# Main.net
KiCad netlist of a schematic drawn in Altium Designer
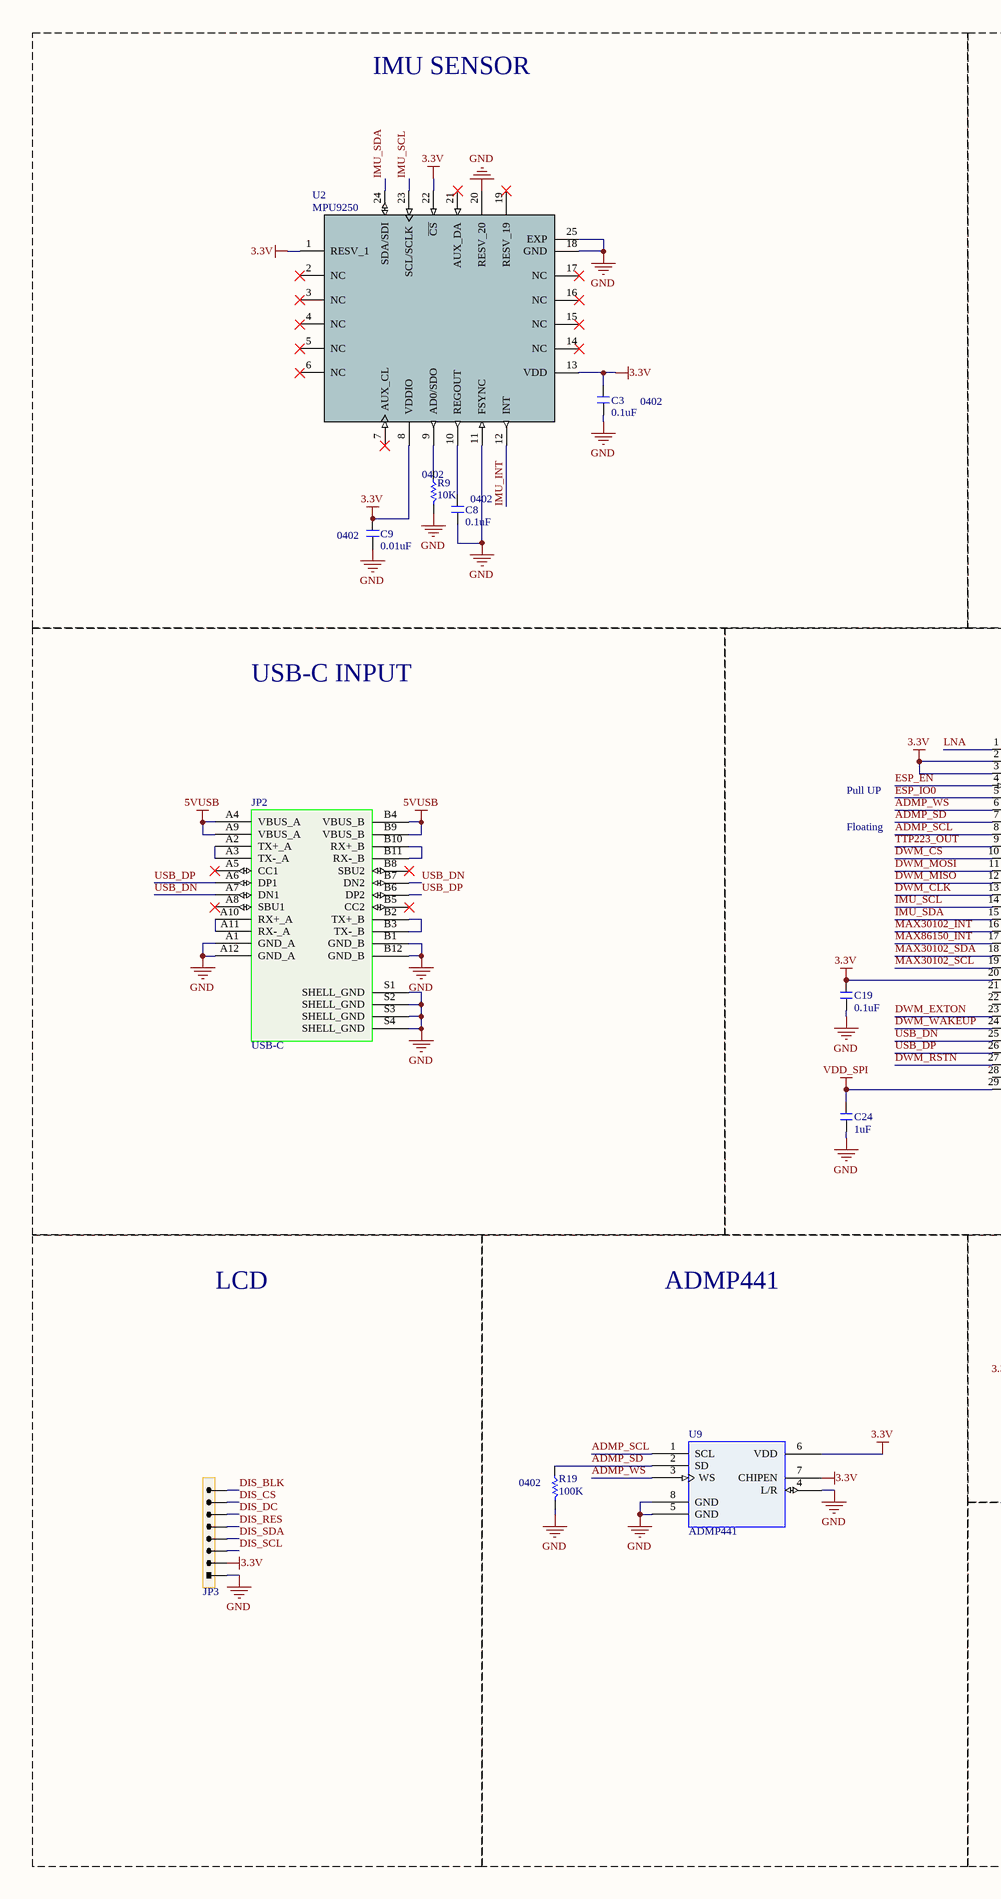
[diagram p0: Main.SchDoc, left]
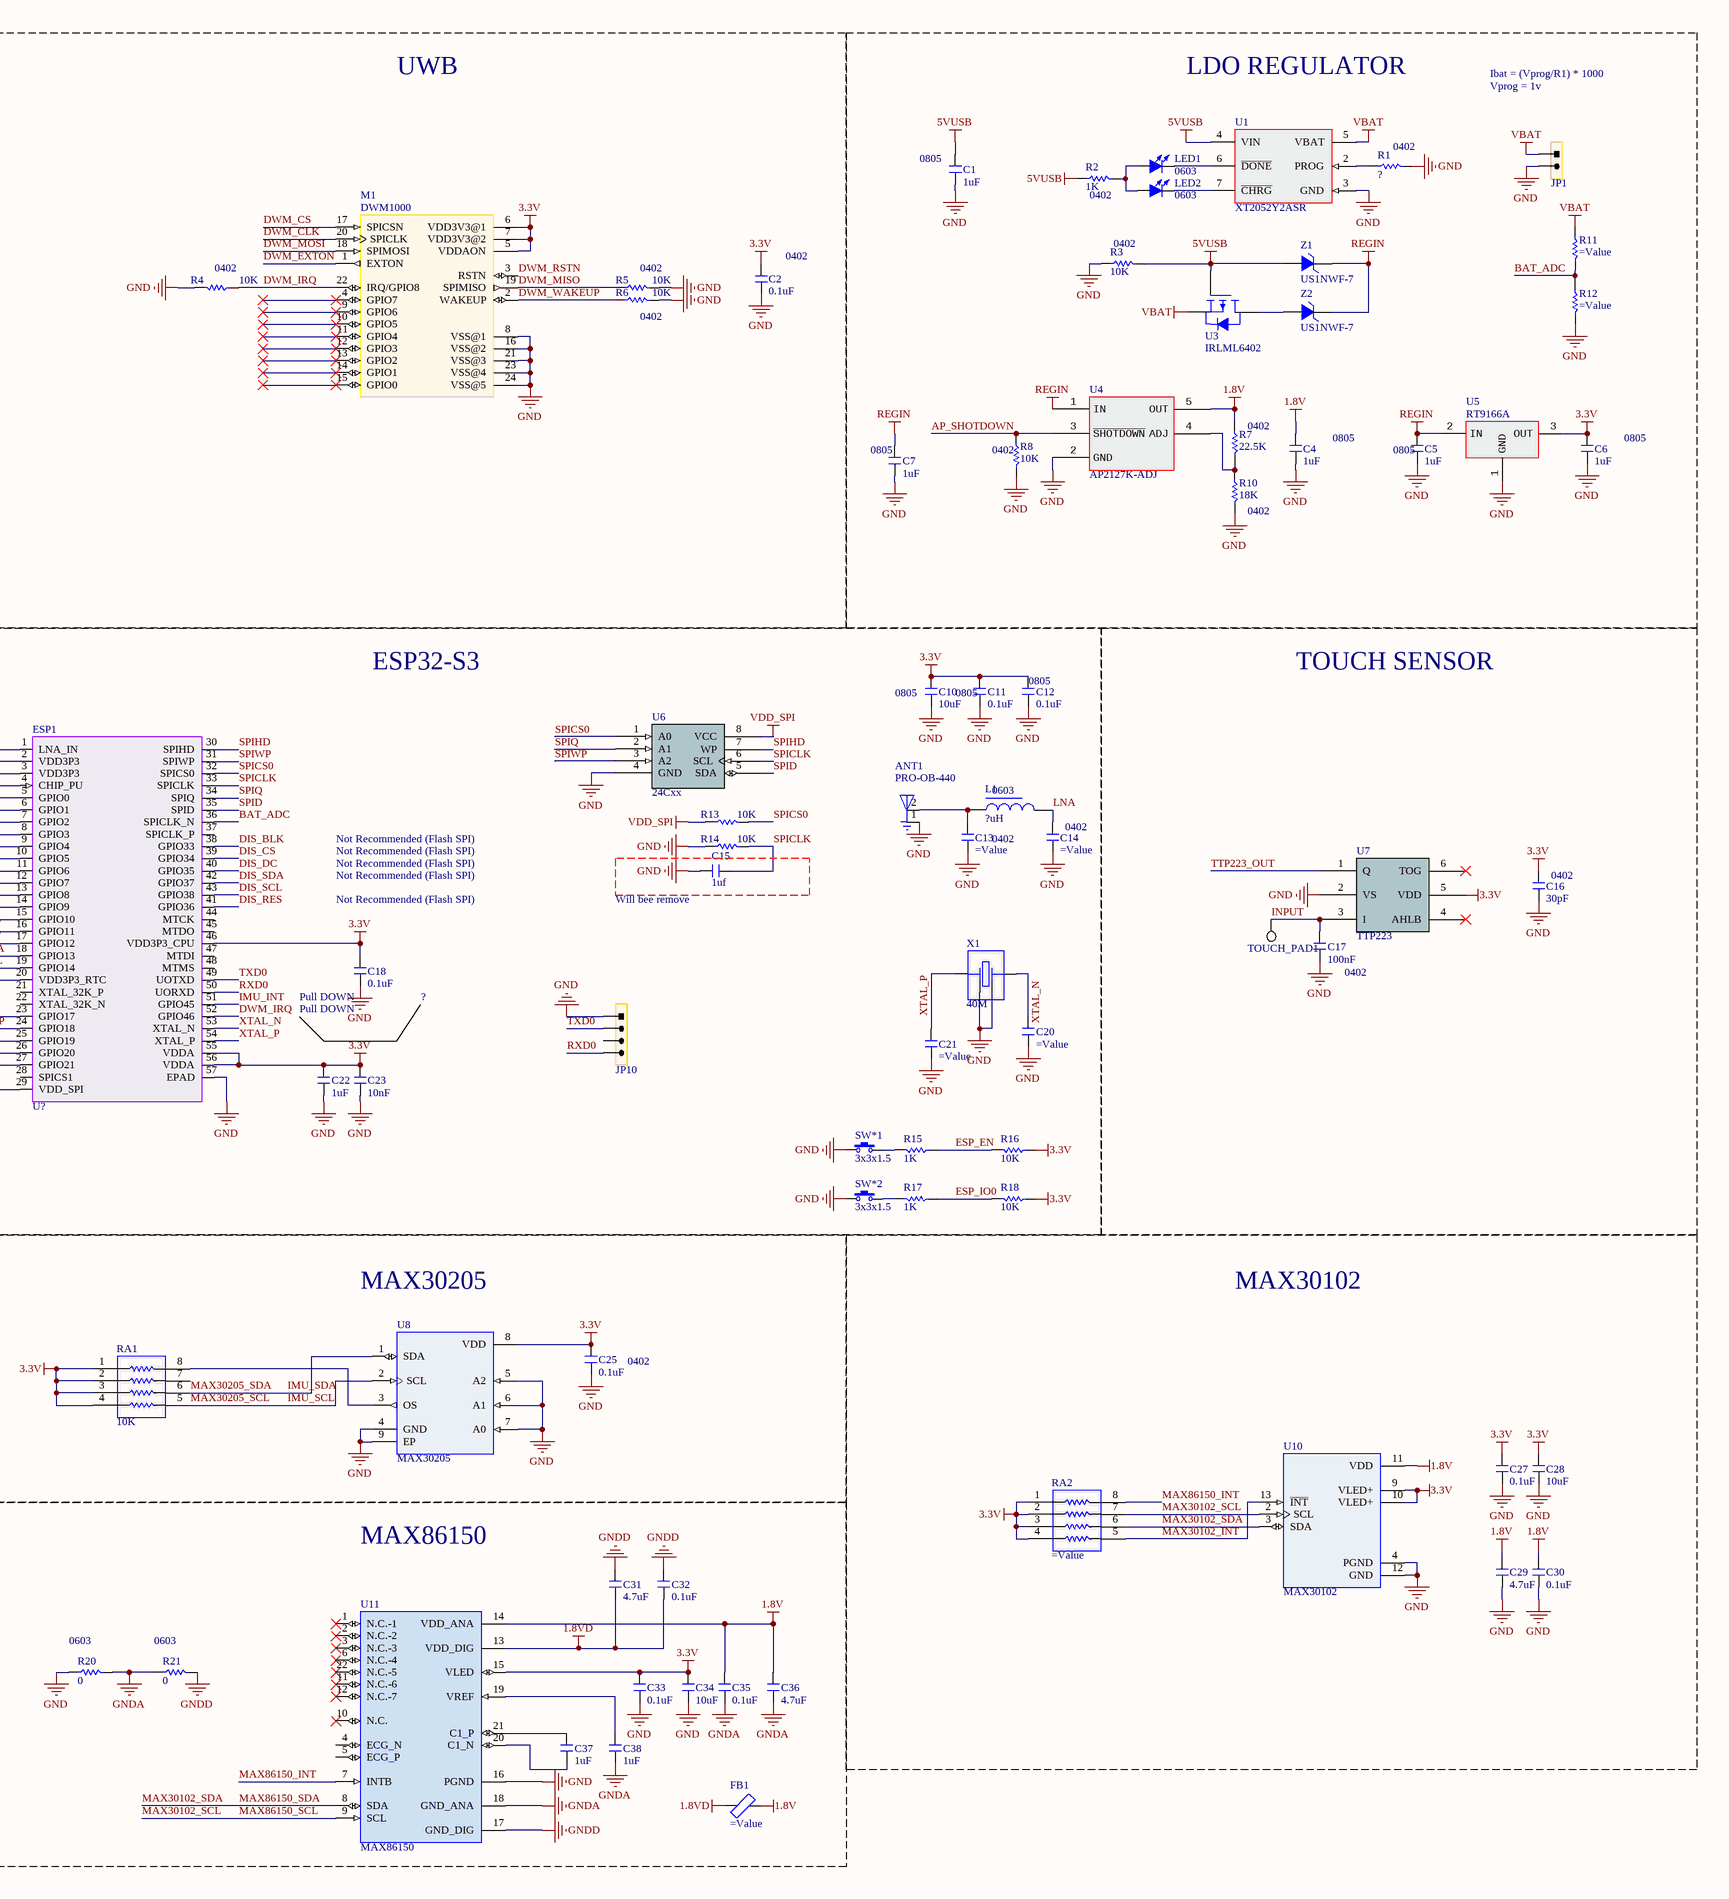
[diagram p1: Main.SchDoc, right]

(export (version "E")
  (design (tool "Eeschema 10.0.6"))
  (components
    (comp (ref "ANT1")
      (value "PRO-OB-440")
      (footprint "PRO-OB-440")
      (libsource (lib "Antenna") (part "PRO-OB-440"))
    )
    (comp (ref "C1")
      (value "1uF")
      (footprint "C 0805")
      (description "Non-polar patch capacitor")
      (fields (field (name "版权归属") "源创客"))
      (libsource (lib "Passive (Resistor-Capacitor-Inductor-Veristor-Ferrite)") (part "C"))
    )
    (comp (ref "C2")
      (value "0.1uF")
      (footprint "C 0402")
      (description "Non-polar patch capacitor")
      (fields (field (name "版权归属") "源创客"))
      (libsource (lib "Passive (Resistor-Capacitor-Inductor-Veristor-Ferrite)") (part "C"))
    )
    (comp (ref "C3")
      (value "0.1uF")
      (footprint "C 0603")
      (description "Non-polar patch capacitor")
      (fields (field (name "版权归属") "源创客"))
      (libsource (lib "Passive (Resistor-Capacitor-Inductor-Veristor-Ferrite)") (part "C"))
    )
    (comp (ref "C4")
      (value "1uF")
      (footprint "C 0805")
      (description "Non-polar patch capacitor")
      (fields (field (name "版权归属") "源创客"))
      (libsource (lib "Passive (Resistor-Capacitor-Inductor-Veristor-Ferrite)") (part "C"))
    )
    (comp (ref "C5")
      (value "1uF")
      (footprint "C 0805")
      (description "Non-polar patch capacitor")
      (fields (field (name "版权归属") "源创客"))
      (libsource (lib "Passive (Resistor-Capacitor-Inductor-Veristor-Ferrite)") (part "C"))
    )
    (comp (ref "C6")
      (value "1uF")
      (footprint "C 0805")
      (description "Non-polar patch capacitor")
      (fields (field (name "版权归属") "源创客"))
      (libsource (lib "Passive (Resistor-Capacitor-Inductor-Veristor-Ferrite)") (part "C"))
    )
    (comp (ref "C7")
      (value "1uF")
      (footprint "C 0805")
      (description "Non-polar patch capacitor")
      (fields (field (name "版权归属") "源创客"))
      (libsource (lib "Passive (Resistor-Capacitor-Inductor-Veristor-Ferrite)") (part "C"))
    )
    (comp (ref "C8")
      (value "0.1uF")
      (footprint "C 0603")
      (description "Non-polar patch capacitor")
      (fields (field (name "版权归属") "源创客"))
      (libsource (lib "Passive (Resistor-Capacitor-Inductor-Veristor-Ferrite)") (part "C"))
    )
    (comp (ref "C9")
      (value "0.01uF")
      (footprint "C 0603")
      (description "Non-polar patch capacitor")
      (fields (field (name "版权归属") "源创客"))
      (libsource (lib "Passive (Resistor-Capacitor-Inductor-Veristor-Ferrite)") (part "C"))
    )
    (comp (ref "C10")
      (value "10uF")
      (footprint "C 0603")
      (description "Non-polar patch capacitor")
      (fields (field (name "版权归属") "源创客"))
      (libsource (lib "Passive (Resistor-Capacitor-Inductor-Veristor-Ferrite)") (part "C"))
    )
    (comp (ref "C11")
      (value "0.1uF")
      (footprint "C 0603")
      (description "Non-polar patch capacitor")
      (fields (field (name "版权归属") "源创客"))
      (libsource (lib "Passive (Resistor-Capacitor-Inductor-Veristor-Ferrite)") (part "C"))
    )
    (comp (ref "C12")
      (value "0.1uF")
      (footprint "C 0603")
      (description "Non-polar patch capacitor")
      (fields (field (name "版权归属") "源创客"))
      (libsource (lib "Passive (Resistor-Capacitor-Inductor-Veristor-Ferrite)") (part "C"))
    )
    (comp (ref "C13")
      (value "~")
      (footprint "C 0402")
      (description "Non-polar patch capacitor")
      (fields (field (name "版权归属") "源创客"))
      (libsource (lib "Passive (Resistor-Capacitor-Inductor-Veristor-Ferrite)") (part "C"))
    )
    (comp (ref "C14")
      (value "~")
      (footprint "C 0402")
      (description "Non-polar patch capacitor")
      (fields (field (name "版权归属") "源创客"))
      (libsource (lib "Passive (Resistor-Capacitor-Inductor-Veristor-Ferrite)") (part "C"))
    )
    (comp (ref "C15")
      (value "1uf")
      (footprint "C 0402")
      (description "Non-polar patch capacitor")
      (fields (field (name "版权归属") "源创客"))
      (libsource (lib "Passive (Resistor-Capacitor-Inductor-Veristor-Ferrite)") (part "C"))
    )
    (comp (ref "C16")
      (value "30pF")
      (footprint "C 0402")
      (description "Non-polar patch capacitor")
      (fields (field (name "版权归属") "源创客"))
      (libsource (lib "Passive (Resistor-Capacitor-Inductor-Veristor-Ferrite)") (part "C"))
    )
    (comp (ref "C17")
      (value "100nF")
      (footprint "C 0402")
      (description "Non-polar patch capacitor")
      (fields (field (name "版权归属") "源创客"))
      (libsource (lib "Passive (Resistor-Capacitor-Inductor-Veristor-Ferrite)") (part "C"))
    )
    (comp (ref "C18")
      (value "0.1uF")
      (footprint "C 0603")
      (description "Non-polar patch capacitor")
      (fields (field (name "版权归属") "源创客"))
      (libsource (lib "Passive (Resistor-Capacitor-Inductor-Veristor-Ferrite)") (part "C"))
    )
    (comp (ref "C19")
      (value "0.1uF")
      (footprint "C 0603")
      (description "Non-polar patch capacitor")
      (fields (field (name "版权归属") "源创客"))
      (libsource (lib "Passive (Resistor-Capacitor-Inductor-Veristor-Ferrite)") (part "C"))
    )
    (comp (ref "C20")
      (value "~")
      (footprint "C 0402")
      (description "Non-polar patch capacitor")
      (fields (field (name "版权归属") "源创客"))
      (libsource (lib "Passive (Resistor-Capacitor-Inductor-Veristor-Ferrite)") (part "C"))
    )
    (comp (ref "C21")
      (value "~")
      (footprint "C 0402")
      (description "Non-polar patch capacitor")
      (fields (field (name "版权归属") "源创客"))
      (libsource (lib "Passive (Resistor-Capacitor-Inductor-Veristor-Ferrite)") (part "C"))
    )
    (comp (ref "C22")
      (value "1uF")
      (footprint "C 0603")
      (description "Non-polar patch capacitor")
      (fields (field (name "版权归属") "源创客"))
      (libsource (lib "Passive (Resistor-Capacitor-Inductor-Veristor-Ferrite)") (part "C"))
    )
    (comp (ref "C23")
      (value "10nF")
      (footprint "C 0603")
      (description "Non-polar patch capacitor")
      (fields (field (name "版权归属") "源创客"))
      (libsource (lib "Passive (Resistor-Capacitor-Inductor-Veristor-Ferrite)") (part "C"))
    )
    (comp (ref "C24")
      (value "1uF")
      (footprint "C 0603")
      (description "Non-polar patch capacitor")
      (fields (field (name "版权归属") "源创客"))
      (libsource (lib "Passive (Resistor-Capacitor-Inductor-Veristor-Ferrite)") (part "C"))
    )
    (comp (ref "C25")
      (value "0.1uF")
      (footprint "C 0603")
      (description "Non-polar patch capacitor")
      (fields (field (name "版权归属") "源创客"))
      (libsource (lib "Passive (Resistor-Capacitor-Inductor-Veristor-Ferrite)") (part "C"))
    )
    (comp (ref "C27")
      (value "0.1uF")
      (footprint "C 0603")
      (description "Non-polar patch capacitor")
      (fields (field (name "版权归属") "源创客"))
      (libsource (lib "Passive (Resistor-Capacitor-Inductor-Veristor-Ferrite)") (part "C"))
    )
    (comp (ref "C28")
      (value "10uF")
      (footprint "C 0603")
      (description "Non-polar patch capacitor")
      (fields (field (name "版权归属") "源创客"))
      (libsource (lib "Passive (Resistor-Capacitor-Inductor-Veristor-Ferrite)") (part "C"))
    )
    (comp (ref "C29")
      (value "4.7uF")
      (footprint "C 0603")
      (description "Non-polar patch capacitor")
      (fields (field (name "版权归属") "源创客"))
      (libsource (lib "Passive (Resistor-Capacitor-Inductor-Veristor-Ferrite)") (part "C"))
    )
    (comp (ref "C30")
      (value "0.1uF")
      (footprint "C 0603")
      (description "Non-polar patch capacitor")
      (fields (field (name "版权归属") "源创客"))
      (libsource (lib "Passive (Resistor-Capacitor-Inductor-Veristor-Ferrite)") (part "C"))
    )
    (comp (ref "C31")
      (value "4.7uF")
      (footprint "C 0603")
      (description "Non-polar patch capacitor")
      (fields (field (name "版权归属") "源创客"))
      (libsource (lib "Passive (Resistor-Capacitor-Inductor-Veristor-Ferrite)") (part "C"))
    )
    (comp (ref "C32")
      (value "0.1uF")
      (footprint "C 0603")
      (description "Non-polar patch capacitor")
      (fields (field (name "版权归属") "源创客"))
      (libsource (lib "Passive (Resistor-Capacitor-Inductor-Veristor-Ferrite)") (part "C"))
    )
    (comp (ref "C33")
      (value "0.1uF")
      (footprint "C 0603")
      (description "Non-polar patch capacitor")
      (fields (field (name "版权归属") "源创客"))
      (libsource (lib "Passive (Resistor-Capacitor-Inductor-Veristor-Ferrite)") (part "C"))
    )
    (comp (ref "C34")
      (value "10uF")
      (footprint "C 0603")
      (description "Non-polar patch capacitor")
      (fields (field (name "版权归属") "源创客"))
      (libsource (lib "Passive (Resistor-Capacitor-Inductor-Veristor-Ferrite)") (part "C"))
    )
    (comp (ref "C35")
      (value "0.1uF")
      (footprint "C 0603")
      (description "Non-polar patch capacitor")
      (fields (field (name "版权归属") "源创客"))
      (libsource (lib "Passive (Resistor-Capacitor-Inductor-Veristor-Ferrite)") (part "C"))
    )
    (comp (ref "C36")
      (value "4.7uF")
      (footprint "C 0603")
      (description "Non-polar patch capacitor")
      (fields (field (name "版权归属") "源创客"))
      (libsource (lib "Passive (Resistor-Capacitor-Inductor-Veristor-Ferrite)") (part "C"))
    )
    (comp (ref "C37")
      (value "1uF")
      (footprint "C 0603")
      (description "Non-polar patch capacitor")
      (fields (field (name "版权归属") "源创客"))
      (libsource (lib "Passive (Resistor-Capacitor-Inductor-Veristor-Ferrite)") (part "C"))
    )
    (comp (ref "C38")
      (value "1uF")
      (footprint "C 0603")
      (description "Non-polar patch capacitor")
      (fields (field (name "版权归属") "源创客"))
      (libsource (lib "Passive (Resistor-Capacitor-Inductor-Veristor-Ferrite)") (part "C"))
    )
    (comp (ref "ESP1")
      (value "U?")
      (footprint "ESP32-S3 CHIP")
      (libsource (lib "Espressif") (part "ESP32-S3 CHIP"))
    )
    (comp (ref "FB1")
      (value "~")
      (footprint "F 0603")
      (description "Ferrite Bead")
      (fields (field (name "版权归属") "源创客"))
      (libsource (lib "Passive (Resistor-Capacitor-Inductor-Veristor-Ferrite)") (part "FB"))
    )
    (comp (ref "JP1")
      (value "HDR-1X2")
      (footprint "PH2.0-2P_H")
      (description "2P Connector")
      (fields (field (name "版权归属") "源创客"))
      (libsource (lib "Connectors") (part "Header 2"))
    )
    (comp (ref "JP2")
      (value "USB-C")
      (footprint "USB-C-RIGHT")
      (libsource (lib "IO (Power-USB-Serial-VGA-RJ-Audio-Buzzer)") (part "USB-C-RIGHT"))
    )
    (comp (ref "JP3")
      (value "HDR-1X8")
      (footprint "HDR-1X8_M")
      (description "8P Connector")
      (fields (field (name "版权归属") "源创客"))
      (libsource (lib "Connectors") (part "Header 8"))
    )
    (comp (ref "JP10")
      (value "HDR-1X4")
      (footprint "HDR-4X1-SMD")
      (description "4P Connector")
      (fields (field (name "版权归属") "源创客"))
      (libsource (lib "Connectors") (part "Header 4"))
    )
    (comp (ref "L1")
      (value "?uH")
      (footprint "L 0603")
      (description "Low power chip inductor")
      (fields (field (name "版权归属") "源创客"))
      (libsource (lib "Passive (Resistor-Capacitor-Inductor-Veristor-Ferrite)") (part "L"))
    )
    (comp (ref "LED1")
      (value "LED-SMD")
      (footprint "LED 0603R")
      (description "Patch LED")
      (fields (field (name "版权归属") "源创客"))
      (libsource (lib "LED") (part "LED-SMD"))
    )
    (comp (ref "LED2")
      (value "LED-SMD")
      (footprint "LED 0603G")
      (description "Patch LED")
      (fields (field (name "版权归属") "源创客"))
      (libsource (lib "LED") (part "LED-SMD"))
    )
    (comp (ref "M1") (value "DWM1000") (footprint "DWM1000") (libsource (lib "Module") (part "DWM1000")))
    (comp (ref "R1")
      (value "?")
      (footprint "R 0402")
      (description "Chip resistor")
      (fields (field (name "版权归属") "源创客"))
      (libsource (lib "Passive (Resistor-Capacitor-Inductor-Veristor-Ferrite)") (part "R"))
    )
    (comp (ref "R2")
      (value "1K")
      (footprint "R 0603")
      (description "Chip resistor")
      (fields (field (name "版权归属") "源创客"))
      (libsource (lib "Passive (Resistor-Capacitor-Inductor-Veristor-Ferrite)") (part "R"))
    )
    (comp (ref "R3")
      (value "10K")
      (footprint "R 0402")
      (description "Chip resistor")
      (fields (field (name "版权归属") "源创客"))
      (libsource (lib "Passive (Resistor-Capacitor-Inductor-Veristor-Ferrite)") (part "R"))
    )
    (comp (ref "R4")
      (value "10K")
      (footprint "R 0402")
      (description "Chip resistor")
      (fields (field (name "版权归属") "源创客"))
      (libsource (lib "Passive (Resistor-Capacitor-Inductor-Veristor-Ferrite)") (part "R"))
    )
    (comp (ref "R5")
      (value "10K")
      (footprint "R 0402")
      (description "Chip resistor")
      (fields (field (name "版权归属") "源创客"))
      (libsource (lib "Passive (Resistor-Capacitor-Inductor-Veristor-Ferrite)") (part "R"))
    )
    (comp (ref "R6")
      (value "10K")
      (footprint "R 0402")
      (description "Chip resistor")
      (fields (field (name "版权归属") "源创客"))
      (libsource (lib "Passive (Resistor-Capacitor-Inductor-Veristor-Ferrite)") (part "R"))
    )
    (comp (ref "R7")
      (value "22.5K")
      (footprint "R 0402")
      (description "Chip resistor")
      (fields (field (name "版权归属") "源创客"))
      (libsource (lib "Passive (Resistor-Capacitor-Inductor-Veristor-Ferrite)") (part "R"))
    )
    (comp (ref "R8")
      (value "10K")
      (footprint "R 0402")
      (description "Chip resistor")
      (fields (field (name "版权归属") "源创客"))
      (libsource (lib "Passive (Resistor-Capacitor-Inductor-Veristor-Ferrite)") (part "R"))
    )
    (comp (ref "R9")
      (value "10K")
      (footprint "R 0603")
      (description "Chip resistor")
      (fields (field (name "版权归属") "源创客"))
      (libsource (lib "Passive (Resistor-Capacitor-Inductor-Veristor-Ferrite)") (part "R"))
    )
    (comp (ref "R10")
      (value "18K")
      (footprint "R 0402")
      (description "Chip resistor")
      (fields (field (name "版权归属") "源创客"))
      (libsource (lib "Passive (Resistor-Capacitor-Inductor-Veristor-Ferrite)") (part "R"))
    )
    (comp (ref "R11")
      (value "~")
      (footprint "R 0402")
      (description "Chip resistor")
      (fields (field (name "版权归属") "源创客"))
      (libsource (lib "Passive (Resistor-Capacitor-Inductor-Veristor-Ferrite)") (part "R"))
    )
    (comp (ref "R12")
      (value "~")
      (footprint "R 0402")
      (description "Chip resistor")
      (fields (field (name "版权归属") "源创客"))
      (libsource (lib "Passive (Resistor-Capacitor-Inductor-Veristor-Ferrite)") (part "R"))
    )
    (comp (ref "R13")
      (value "10K")
      (footprint "R 0402")
      (description "Chip resistor")
      (fields (field (name "版权归属") "源创客"))
      (libsource (lib "Passive (Resistor-Capacitor-Inductor-Veristor-Ferrite)") (part "R"))
    )
    (comp (ref "R14")
      (value "10K")
      (footprint "R 0402")
      (description "Chip resistor")
      (fields (field (name "版权归属") "源创客"))
      (libsource (lib "Passive (Resistor-Capacitor-Inductor-Veristor-Ferrite)") (part "R"))
    )
    (comp (ref "R15")
      (value "1K")
      (footprint "R 0603-HP")
      (description "Chip resistor")
      (fields (field (name "版权归属") "源创客"))
      (libsource (lib "Passive (Resistor-Capacitor-Inductor-Veristor-Ferrite)") (part "R"))
    )
    (comp (ref "R16")
      (value "10K")
      (footprint "R 0603-HP")
      (description "Chip resistor")
      (fields (field (name "版权归属") "源创客"))
      (libsource (lib "Passive (Resistor-Capacitor-Inductor-Veristor-Ferrite)") (part "R"))
    )
    (comp (ref "R17")
      (value "1K")
      (footprint "R 0603-HP")
      (description "Chip resistor")
      (fields (field (name "版权归属") "源创客"))
      (libsource (lib "Passive (Resistor-Capacitor-Inductor-Veristor-Ferrite)") (part "R"))
    )
    (comp (ref "R18")
      (value "10K")
      (footprint "R 0603-HP")
      (description "Chip resistor")
      (fields (field (name "版权归属") "源创客"))
      (libsource (lib "Passive (Resistor-Capacitor-Inductor-Veristor-Ferrite)") (part "R"))
    )
    (comp (ref "R19")
      (value "100K")
      (footprint "R 0402")
      (description "Chip resistor")
      (fields (field (name "版权归属") "源创客"))
      (libsource (lib "Passive (Resistor-Capacitor-Inductor-Veristor-Ferrite)") (part "R"))
    )
    (comp (ref "R20")
      (value "0")
      (footprint "R 0603")
      (description "Chip resistor")
      (fields (field (name "版权归属") "源创客"))
      (libsource (lib "Passive (Resistor-Capacitor-Inductor-Veristor-Ferrite)") (part "R"))
    )
    (comp (ref "R21")
      (value "0")
      (footprint "R 0603")
      (description "Chip resistor")
      (fields (field (name "版权归属") "源创客"))
      (libsource (lib "Passive (Resistor-Capacitor-Inductor-Veristor-Ferrite)") (part "R"))
    )
    (comp (ref "RA1")
      (value "10K")
      (footprint "RA1206 (4x0603)")
      (description "4 way Chip Resistor Array")
      (libsource (lib "Passive (Resistor-Capacitor-Inductor-Veristor-Ferrite)") (part "R-ARR"))
    )
    (comp (ref "RA2")
      (value "~")
      (footprint "RA1206 (4x0603)")
      (description "4 way Chip Resistor Array")
      (libsource (lib "Passive (Resistor-Capacitor-Inductor-Veristor-Ferrite)") (part "R-ARR"))
    )
    (comp (ref "SW*1")
      (value "3x3x1.5")
      (footprint "TSW SMD-3*3")
      (description "3x3 tact switch")
      (libsource (lib "Button") (part "TSW 3x3"))
    )
    (comp (ref "SW*2")
      (value "3x3x1.5")
      (footprint "TSW SMD-3*3")
      (description "3x3 tact switch")
      (libsource (lib "Button") (part "TSW 3x3"))
    )
    (comp (ref "TOUCH_PAD1")
      (value "Test Point Pad")
      (footprint "TP07SQ")
      (fields (field (name "DESIGNER") "Eng. Saeid Jorablo"))
      (libsource (lib "Test Point") (part "Test Point Pad"))
    )
    (comp (ref "U1")
      (value "XT2052Y2ASR")
      (footprint "SOP8_M-EP")
      (libsource (lib "Integrated Circuit") (part "XT2052Y2ASR"))
    )
    (comp (ref "U2")
      (value "MPU9250")
      (footprint "QFN40-25N")
      (libsource (lib "Integrated Circuit") (part "MPU9250"))
    )
    (comp (ref "U3")
      (value "IRLML6402")
      (footprint "SOT23-3L")
      (description "P-Channel")
      (libsource (lib "Transistor") (part "IRLML6402"))
    )
    (comp (ref "U4")
      (value "AP2127K-ADJ")
      (footprint "SOT23-5L")
      (libsource (lib "Integrated Circuit") (part "AP2127K-ADJ"))
    )
    (comp (ref "U5")
      (value "RT9166A")
      (footprint "SOT89_M")
      (libsource (lib "Integrated Circuit") (part "RT9166A-33GXL"))
    )
    (comp (ref "U6")
      (value "24Cxx")
      (footprint "SOP8_L")
      (description "Two-wire Serial EEPROM")
      (fields (field (name "版权归属") "源创客"))
      (libsource (lib "Integrated Circuit") (part "24Cxx"))
    )
    (comp (ref "U7")
      (value "TTP223")
      (footprint "SOT23-6L")
      (libsource (lib "Integrated Circuit") (part "TTP223"))
    )
    (comp (ref "U8")
      (value "MAX30205")
      (footprint "MAX30205")
      (description "Body Temprature")
      (libsource (lib "Sensing Element") (part "MAX30205"))
    )
    (comp (ref "U9")
      (value "ADMP441")
      (footprint "ADMP441")
      (libsource (lib "Sensing Element") (part "ADMP441"))
    )
    (comp (ref "U10")
      (value "MAX30102")
      (footprint "MAX30102")
      (libsource (lib "Sensing Element") (part "MAX30102"))
    )
    (comp (ref "U11")
      (value "MAX86150")
      (footprint "MAX86150")
      (libsource (lib "Sensing Element") (part "MAX86150EFF+"))
    )
    (comp (ref "X1")
      (value "40M")
      (footprint "XTAL-3225-4")
      (description "4-Pin crystal")
      (fields (field (name "版权归属") "源创客"))
      (libsource (lib "Crystal Oscillator") (part "XTAL-4"))
    )
    (comp (ref "Z1")
      (value "US1NWF-7")
      (footprint "DO-213AA")
      (description "12V/0.5W voltage regulator")
      (fields (field (name "版权归属") "源创客"))
      (libsource (lib "Diode-Zener-Rectifier Bridge") (part "1N4106"))
    )
    (comp (ref "Z2")
      (value "US1NWF-7")
      (footprint "DO-213AA")
      (description "12V/0.5W voltage regulator")
      (fields (field (name "版权归属") "源创客"))
      (libsource (lib "Diode-Zener-Rectifier Bridge") (part "1N4106"))
    )
  )
  (nets
    (net (code "1") (name "/ADMP_SCL") (class "Default")
      (node (ref "ESP1") (pin "8") (pinfunction "GPIO3_8") (pintype "bidirectional"))
      (node (ref "U9") (pin "1") (pinfunction "SCL_1") (pintype "passive"))
    )
    (net (code "2") (name "/ADMP_SD") (class "Default")
      (node (ref "ESP1") (pin "7") (pinfunction "GPIO2_7") (pintype "bidirectional"))
      (node (ref "R19") (pin "1") (pinfunction "1_1") (pintype "passive"))
      (node (ref "U9") (pin "2") (pinfunction "SD_2") (pintype "power_in"))
    )
    (net (code "3") (name "/ADMP_WS") (class "Default")
      (node (ref "ESP1") (pin "6") (pinfunction "GPIO1_6") (pintype "bidirectional"))
      (node (ref "U9") (pin "3") (pinfunction "WS_3") (pintype "input"))
    )
    (net (code "4") (name "/AP_SHOTDOWN") (class "Default")
      (node (ref "R8") (pin "1") (pinfunction "1_1") (pintype "passive"))
      (node (ref "U4") (pin "3") (pinfunction "~{SHOTDOWN}_3") (pintype "power_in"))
    )
    (net (code "5") (name "/BAT_ADC") (class "Default")
      (node (ref "ESP1") (pin "36") (pinfunction "SPICLK_N_36") (pintype "bidirectional"))
      (node (ref "R11") (pin "2") (pinfunction "2_2") (pintype "passive"))
      (node (ref "R12") (pin "1") (pinfunction "1_1") (pintype "passive"))
    )
    (net (code "6") (name "/DIS_BLK") (class "Default")
      (node (ref "ESP1") (pin "38") (pinfunction "GPIO33_38") (pintype "bidirectional"))
      (node (ref "JP3") (pin "8") (pintype "passive"))
    )
    (net (code "7") (name "/DIS_CS") (class "Default")
      (node (ref "ESP1") (pin "39") (pinfunction "GPIO34_39") (pintype "bidirectional"))
      (node (ref "JP3") (pin "7") (pintype "passive"))
    )
    (net (code "8") (name "/DIS_DC") (class "Default")
      (node (ref "ESP1") (pin "40") (pinfunction "GPIO35_40") (pintype "bidirectional"))
      (node (ref "JP3") (pin "6") (pintype "passive"))
    )
    (net (code "9") (name "/DIS_RES") (class "Default")
      (node (ref "ESP1") (pin "41") (pinfunction "GPIO36_41") (pintype "bidirectional"))
      (node (ref "JP3") (pin "5") (pintype "passive"))
    )
    (net (code "10") (name "/DIS_SCL") (class "Default")
      (node (ref "ESP1") (pin "43") (pinfunction "GPIO38_43") (pintype "bidirectional"))
      (node (ref "JP3") (pin "3") (pintype "passive"))
    )
    (net (code "11") (name "/DIS_SDA") (class "Default")
      (node (ref "ESP1") (pin "42") (pinfunction "GPIO37_42") (pintype "bidirectional"))
      (node (ref "JP3") (pin "4") (pintype "passive"))
    )
    (net (code "12") (name "/DWM_CLK") (class "Default")
      (node (ref "ESP1") (pin "13") (pinfunction "GPIO8_13") (pintype "bidirectional"))
      (node (ref "M1") (pin "20") (pinfunction "SPICLK_20") (pintype "input"))
    )
    (net (code "13") (name "/DWM_CS") (class "Default")
      (node (ref "ESP1") (pin "10") (pinfunction "GPIO5_10") (pintype "bidirectional"))
      (node (ref "M1") (pin "17") (pinfunction "SPICSN_17") (pintype "input"))
    )
    (net (code "14") (name "/DWM_EXTON") (class "Default")
      (node (ref "ESP1") (pin "23") (pinfunction "GPIO17_23") (pintype "bidirectional"))
      (node (ref "M1") (pin "1") (pinfunction "EXTON_1") (pintype "output"))
    )
    (net (code "15") (name "/DWM_IRQ") (class "Default")
      (node (ref "ESP1") (pin "52") (pinfunction "GPIO46_52") (pintype "bidirectional"))
      (node (ref "M1") (pin "22") (pinfunction "IRQ/GPIO8_22") (pintype "bidirectional"))
      (node (ref "R4") (pin "1") (pinfunction "1_1") (pintype "passive"))
    )
    (net (code "16") (name "/DWM_MISO") (class "Default")
      (node (ref "ESP1") (pin "12") (pinfunction "GPIO7_12") (pintype "bidirectional"))
      (node (ref "M1") (pin "19") (pinfunction "SPIMISO_19") (pintype "output"))
      (node (ref "R5") (pin "1") (pinfunction "1_1") (pintype "passive"))
    )
    (net (code "17") (name "/DWM_MOSI") (class "Default")
      (node (ref "ESP1") (pin "11") (pinfunction "GPIO6_11") (pintype "bidirectional"))
      (node (ref "M1") (pin "18") (pinfunction "SPIMOSI_18") (pintype "input"))
    )
    (net (code "18") (name "/DWM_RSTN") (class "Default")
      (node (ref "ESP1") (pin "27") (pinfunction "GPIO21_27") (pintype "bidirectional"))
      (node (ref "M1") (pin "3") (pinfunction "RSTN_3") (pintype "bidirectional"))
    )
    (net (code "19") (name "/DWM_WAKEUP") (class "Default")
      (node (ref "ESP1") (pin "24") (pinfunction "GPIO18_24") (pintype "bidirectional"))
      (node (ref "M1") (pin "2") (pinfunction "WAKEUP_2") (pintype "bidirectional"))
      (node (ref "R6") (pin "1") (pinfunction "1_1") (pintype "passive"))
    )
    (net (code "20") (name "/ESP_EN") (class "Default")
      (node (ref "ESP1") (pin "4") (pinfunction "CHIP_PU_4") (pintype "input"))
      (node (ref "R15") (pin "1") (pinfunction "1_1") (pintype "passive"))
      (node (ref "R16") (pin "2") (pinfunction "2_2") (pintype "passive"))
    )
    (net (code "21") (name "/ESP_IO0") (class "Default")
      (node (ref "ESP1") (pin "5") (pinfunction "GPIO0_5") (pintype "bidirectional"))
      (node (ref "R17") (pin "1") (pinfunction "1_1") (pintype "passive"))
      (node (ref "R18") (pin "2") (pinfunction "2_2") (pintype "passive"))
    )
    (net (code "22") (name "/IMU_INT") (class "Default")
      (node (ref "ESP1") (pin "51") (pinfunction "GPIO45_51") (pintype "bidirectional"))
      (node (ref "U2") (pin "12") (pinfunction "INT_12") (pintype "output"))
    )
    (net (code "23") (name "/IMU_SCL") (class "Default")
      (node (ref "ESP1") (pin "14") (pinfunction "GPIO9_14") (pintype "bidirectional"))
      (node (ref "RA1") (pin "5") (pinfunction "5_5") (pintype "passive"))
      (node (ref "U2") (pin "23") (pinfunction "SCL/SCLK_23") (pintype "input"))
      (node (ref "U8") (pin "2") (pinfunction "SCL_2") (pintype "input"))
    )
    (net (code "24") (name "/IMU_SDA") (class "Default")
      (node (ref "ESP1") (pin "15") (pinfunction "GPIO10_15") (pintype "bidirectional"))
      (node (ref "RA1") (pin "6") (pinfunction "6_6") (pintype "passive"))
      (node (ref "U2") (pin "24") (pinfunction "SDA/SDI_24") (pintype "bidirectional"))
      (node (ref "U8") (pin "1") (pinfunction "SDA_1") (pintype "bidirectional"))
    )
    (net (code "25") (name "/INPUT") (class "Default")
      (node (ref "C17") (pin "1") (pinfunction "1_1") (pintype "passive"))
      (node (ref "TOUCH_PAD1") (pin "1") (pinfunction "1_1") (pintype "passive"))
      (node (ref "U7") (pin "3") (pinfunction "I_3") (pintype "passive"))
    )
    (net (code "26") (name "/LNA") (class "Default")
      (node (ref "C14") (pin "1") (pinfunction "1_1") (pintype "passive"))
      (node (ref "ESP1") (pin "1") (pinfunction "LNA_IN_1") (pintype "bidirectional"))
      (node (ref "L1") (pin "2") (pinfunction "2_2") (pintype "passive"))
    )
    (net (code "27") (name "/MAX30102_INT") (class "Default")
      (node (ref "ESP1") (pin "16") (pinfunction "GPIO11_16") (pintype "bidirectional"))
      (node (ref "RA2") (pin "5") (pinfunction "5_5") (pintype "passive"))
      (node (ref "U10") (pin "13") (pinfunction "~{INT}_13") (pintype "input"))
    )
    (net (code "28") (name "/MAX30102_SCL") (class "Default")
      (node (ref "ESP1") (pin "19") (pinfunction "GPIO14_19") (pintype "bidirectional"))
      (node (ref "RA2") (pin "7") (pinfunction "7_7") (pintype "passive"))
      (node (ref "U10") (pin "2") (pinfunction "SCL_2") (pintype "input"))
      (node (ref "U11") (pin "9") (pinfunction "SCL_9") (pintype "input"))
    )
    (net (code "29") (name "/MAX30102_SDA") (class "Default")
      (node (ref "ESP1") (pin "18") (pinfunction "GPIO13_18") (pintype "bidirectional"))
      (node (ref "RA2") (pin "6") (pinfunction "6_6") (pintype "passive"))
      (node (ref "U10") (pin "3") (pinfunction "SDA_3") (pintype "bidirectional"))
      (node (ref "U11") (pin "8") (pinfunction "SDA_8") (pintype "bidirectional"))
    )
    (net (code "30") (name "/MAX86150_INT") (class "Default")
      (node (ref "ESP1") (pin "17") (pinfunction "GPIO12_17") (pintype "bidirectional"))
      (node (ref "RA2") (pin "8") (pinfunction "8_8") (pintype "passive"))
      (node (ref "U11") (pin "7") (pinfunction "INTB_7") (pintype "input"))
    )
    (net (code "31") (name "/RXD0") (class "Default")
      (node (ref "ESP1") (pin "50") (pinfunction "UORXD_50") (pintype "bidirectional"))
      (node (ref "JP10") (pin "4") (pintype "passive"))
    )
    (net (code "32") (name "/SPICLK") (class "Default")
      (node (ref "C15") (pin "2") (pinfunction "2_2") (pintype "passive"))
      (node (ref "ESP1") (pin "33") (pinfunction "SPICLK_33") (pintype "bidirectional"))
      (node (ref "R14") (pin "2") (pinfunction "2_2") (pintype "passive"))
      (node (ref "U6") (pin "6") (pinfunction "SCL_6") (pintype "input"))
    )
    (net (code "33") (name "/SPICS0") (class "Default")
      (node (ref "ESP1") (pin "32") (pinfunction "SPICS0_32") (pintype "bidirectional"))
      (node (ref "R13") (pin "2") (pinfunction "2_2") (pintype "passive"))
      (node (ref "U6") (pin "1") (pinfunction "A0_1") (pintype "input"))
    )
    (net (code "34") (name "/SPID") (class "Default")
      (node (ref "ESP1") (pin "35") (pinfunction "SPID_35") (pintype "bidirectional"))
      (node (ref "U6") (pin "5") (pinfunction "SDA_5") (pintype "bidirectional"))
    )
    (net (code "35") (name "/SPIHD") (class "Default")
      (node (ref "ESP1") (pin "30") (pinfunction "SPIHD_30") (pintype "bidirectional"))
      (node (ref "U6") (pin "7") (pinfunction "WP_7") (pintype "passive"))
    )
    (net (code "36") (name "/SPIQ") (class "Default")
      (node (ref "ESP1") (pin "34") (pinfunction "SPIQ_34") (pintype "bidirectional"))
      (node (ref "U6") (pin "2") (pinfunction "A1_2") (pintype "input"))
    )
    (net (code "37") (name "/SPIWP") (class "Default")
      (node (ref "ESP1") (pin "31") (pinfunction "SPIWP_31") (pintype "bidirectional"))
      (node (ref "U6") (pin "3") (pinfunction "A2_3") (pintype "input"))
    )
    (net (code "38") (name "/TTP223_OUT") (class "Default")
      (node (ref "ESP1") (pin "9") (pinfunction "GPIO4_9") (pintype "bidirectional"))
      (node (ref "U7") (pin "1") (pinfunction "Q_1") (pintype "passive"))
    )
    (net (code "39") (name "/TXD0") (class "Default")
      (node (ref "ESP1") (pin "49") (pinfunction "UOTXD_49") (pintype "bidirectional"))
      (node (ref "JP10") (pin "2") (pintype "passive"))
    )
    (net (code "40") (name "/USB_DN") (class "Default")
      (node (ref "ESP1") (pin "25") (pinfunction "GPIO19_25") (pintype "bidirectional"))
      (node (ref "JP2") (pin "A7") (pinfunction "DN1_A7") (pintype "bidirectional"))
      (node (ref "JP2") (pin "B7") (pinfunction "DN2_B7") (pintype "bidirectional"))
    )
    (net (code "41") (name "/USB_DP") (class "Default")
      (node (ref "ESP1") (pin "26") (pinfunction "GPIO20_26") (pintype "bidirectional"))
      (node (ref "JP2") (pin "A6") (pinfunction "DP1_A6") (pintype "bidirectional"))
      (node (ref "JP2") (pin "B6") (pinfunction "DP2_B6") (pintype "bidirectional"))
    )
    (net (code "42") (name "/XTAL_N") (class "Default")
      (node (ref "C20") (pin "1") (pinfunction "1_1") (pintype "passive"))
      (node (ref "ESP1") (pin "53") (pinfunction "XTAL_N_53") (pintype "passive"))
      (node (ref "X1") (pin "3") (pinfunction "3_3") (pintype "passive"))
    )
    (net (code "43") (name "/XTAL_P") (class "Default")
      (node (ref "C21") (pin "1") (pinfunction "1_1") (pintype "passive"))
      (node (ref "ESP1") (pin "54") (pinfunction "XTAL_P_54") (pintype "passive"))
      (node (ref "X1") (pin "1") (pinfunction "1_1") (pintype "passive"))
    )
    (net (code "44") (name "1.8V") (class "Default")
      (node (ref "C29") (pin "1") (pinfunction "1_1") (pintype "passive"))
      (node (ref "C30") (pin "1") (pinfunction "1_1") (pintype "passive"))
      (node (ref "C35") (pin "1") (pinfunction "1_1") (pintype "passive"))
      (node (ref "C36") (pin "1") (pinfunction "1_1") (pintype "passive"))
      (node (ref "C4") (pin "1") (pinfunction "1_1") (pintype "passive"))
      (node (ref "FB1") (pin "2") (pinfunction "2_2") (pintype "passive"))
      (node (ref "R7") (pin "1") (pinfunction "1_1") (pintype "passive"))
      (node (ref "U10") (pin "11") (pinfunction "VDD_11") (pintype "power_in"))
      (node (ref "U11") (pin "14") (pinfunction "VDD_ANA_14") (pintype "power_in"))
      (node (ref "U4") (pin "5") (pinfunction "OUT_5") (pintype "power_in"))
    )
    (net (code "45") (name "1.8VD") (class "Default")
      (node (ref "C31") (pin "2") (pinfunction "2_2") (pintype "passive"))
      (node (ref "C32") (pin "2") (pinfunction "2_2") (pintype "passive"))
      (node (ref "FB1") (pin "1") (pinfunction "1_1") (pintype "passive"))
      (node (ref "U11") (pin "13") (pinfunction "VDD_DIG_13") (pintype "power_in"))
    )
    (net (code "46") (name "3.3V") (class "Default")
      (node (ref "C10") (pin "1") (pinfunction "1_1") (pintype "passive"))
      (node (ref "C11") (pin "1") (pinfunction "1_1") (pintype "passive"))
      (node (ref "C12") (pin "1") (pinfunction "1_1") (pintype "passive"))
      (node (ref "C16") (pin "1") (pinfunction "1_1") (pintype "passive"))
      (node (ref "C18") (pin "1") (pinfunction "1_1") (pintype "passive"))
      (node (ref "C19") (pin "1") (pinfunction "1_1") (pintype "passive"))
      (node (ref "C2") (pin "2") (pinfunction "2_2") (pintype "passive"))
      (node (ref "C22") (pin "1") (pinfunction "1_1") (pintype "passive"))
      (node (ref "C23") (pin "1") (pinfunction "1_1") (pintype "passive"))
      (node (ref "C25") (pin "1") (pinfunction "1_1") (pintype "passive"))
      (node (ref "C27") (pin "1") (pinfunction "1_1") (pintype "passive"))
      (node (ref "C28") (pin "1") (pinfunction "1_1") (pintype "passive"))
      (node (ref "C3") (pin "1") (pinfunction "1_1") (pintype "passive"))
      (node (ref "C33") (pin "1") (pinfunction "1_1") (pintype "passive"))
      (node (ref "C34") (pin "1") (pinfunction "1_1") (pintype "passive"))
      (node (ref "C6") (pin "1") (pinfunction "1_1") (pintype "passive"))
      (node (ref "C9") (pin "1") (pinfunction "1_1") (pintype "passive"))
      (node (ref "ESP1") (pin "2") (pinfunction "VDD3P3_2") (pintype "power_in"))
      (node (ref "ESP1") (pin "20") (pinfunction "VDD3P3_RTC_20") (pintype "power_in"))
      (node (ref "ESP1") (pin "3") (pinfunction "VDD3P3_3") (pintype "power_in"))
      (node (ref "ESP1") (pin "46") (pinfunction "VDD3P3_CPU_46") (pintype "power_in"))
      (node (ref "ESP1") (pin "55") (pinfunction "VDDA_55") (pintype "power_in"))
      (node (ref "ESP1") (pin "56") (pinfunction "VDDA_56") (pintype "power_in"))
      (node (ref "JP3") (pin "2") (pintype "passive"))
      (node (ref "M1") (pin "5") (pinfunction "VDDAON_5") (pintype "power_in"))
      (node (ref "M1") (pin "6") (pinfunction "VDD3V3@1_6") (pintype "power_in"))
      (node (ref "M1") (pin "7") (pinfunction "VDD3V3@2_7") (pintype "power_in"))
      (node (ref "R16") (pin "1") (pinfunction "1_1") (pintype "passive"))
      (node (ref "R18") (pin "1") (pinfunction "1_1") (pintype "passive"))
      (node (ref "RA1") (pin "1") (pinfunction "1_1") (pintype "passive"))
      (node (ref "RA1") (pin "2") (pinfunction "2_2") (pintype "passive"))
      (node (ref "RA1") (pin "3") (pinfunction "3_3") (pintype "passive"))
      (node (ref "RA1") (pin "4") (pinfunction "4_4") (pintype "passive"))
      (node (ref "RA2") (pin "1") (pinfunction "1_1") (pintype "passive"))
      (node (ref "RA2") (pin "2") (pinfunction "2_2") (pintype "passive"))
      (node (ref "RA2") (pin "3") (pinfunction "3_3") (pintype "passive"))
      (node (ref "RA2") (pin "4") (pinfunction "4_4") (pintype "passive"))
      (node (ref "U10") (pin "10") (pinfunction "VLED+_10") (pintype "power_in"))
      (node (ref "U10") (pin "9") (pinfunction "VLED+_9") (pintype "power_in"))
      (node (ref "U11") (pin "15") (pinfunction "VLED_15") (pintype "bidirectional"))
      (node (ref "U2") (pin "1") (pinfunction "RESV_1_1") (pintype "power_in"))
      (node (ref "U2") (pin "13") (pinfunction "VDD_13") (pintype "power_in"))
      (node (ref "U2") (pin "22") (pinfunction "~{CS}_22") (pintype "input"))
      (node (ref "U2") (pin "8") (pinfunction "VDDIO_8") (pintype "power_in"))
      (node (ref "U5") (pin "3") (pinfunction "OUT_3") (pintype "power_in"))
      (node (ref "U7") (pin "5") (pinfunction "VDD_5") (pintype "passive"))
      (node (ref "U8") (pin "8") (pinfunction "VDD_8") (pintype "power_in"))
      (node (ref "U9") (pin "6") (pinfunction "VDD_6") (pintype "passive"))
      (node (ref "U9") (pin "7") (pinfunction "CHIPEN_7") (pintype "passive"))
    )
    (net (code "47") (name "5VUSB") (class "Default")
      (node (ref "C1") (pin "1") (pinfunction "1_1") (pintype "passive"))
      (node (ref "JP2") (pin "A4") (pinfunction "VBUS_A_A4") (pintype "power_in"))
      (node (ref "JP2") (pin "A9") (pinfunction "VBUS_A_A9") (pintype "power_in"))
      (node (ref "JP2") (pin "B4") (pinfunction "VBUS_B_B4") (pintype "power_in"))
      (node (ref "JP2") (pin "B9") (pinfunction "VBUS_B_B9") (pintype "power_in"))
      (node (ref "R2") (pin "1") (pinfunction "1_1") (pintype "passive"))
      (node (ref "R3") (pin "2") (pinfunction "2_2") (pintype "passive"))
      (node (ref "U1") (pin "4") (pinfunction "VIN_4") (pintype "power_in"))
      (node (ref "U3") (pin "1") (pinfunction "G_1") (pintype "passive"))
      (node (ref "Z1") (pin "1") (pinfunction "A_1") (pintype "passive"))
    )
    (net (code "48") (name "GND") (class "Default")
      (node (ref "ANT1") (pin "1") (pinfunction "GND_1") (pintype "power_in"))
      (node (ref "C1") (pin "2") (pinfunction "2_2") (pintype "passive"))
      (node (ref "C10") (pin "2") (pinfunction "2_2") (pintype "passive"))
      (node (ref "C11") (pin "2") (pinfunction "2_2") (pintype "passive"))
      (node (ref "C12") (pin "2") (pinfunction "2_2") (pintype "passive"))
      (node (ref "C13") (pin "2") (pinfunction "2_2") (pintype "passive"))
      (node (ref "C14") (pin "2") (pinfunction "2_2") (pintype "passive"))
      (node (ref "C15") (pin "1") (pinfunction "1_1") (pintype "passive"))
      (node (ref "C16") (pin "2") (pinfunction "2_2") (pintype "passive"))
      (node (ref "C17") (pin "2") (pinfunction "2_2") (pintype "passive"))
      (node (ref "C18") (pin "2") (pinfunction "2_2") (pintype "passive"))
      (node (ref "C19") (pin "2") (pinfunction "2_2") (pintype "passive"))
      (node (ref "C2") (pin "1") (pinfunction "1_1") (pintype "passive"))
      (node (ref "C20") (pin "2") (pinfunction "2_2") (pintype "passive"))
      (node (ref "C21") (pin "2") (pinfunction "2_2") (pintype "passive"))
      (node (ref "C22") (pin "2") (pinfunction "2_2") (pintype "passive"))
      (node (ref "C23") (pin "2") (pinfunction "2_2") (pintype "passive"))
      (node (ref "C24") (pin "2") (pinfunction "2_2") (pintype "passive"))
      (node (ref "C25") (pin "2") (pinfunction "2_2") (pintype "passive"))
      (node (ref "C27") (pin "2") (pinfunction "2_2") (pintype "passive"))
      (node (ref "C28") (pin "2") (pinfunction "2_2") (pintype "passive"))
      (node (ref "C29") (pin "2") (pinfunction "2_2") (pintype "passive"))
      (node (ref "C3") (pin "2") (pinfunction "2_2") (pintype "passive"))
      (node (ref "C30") (pin "2") (pinfunction "2_2") (pintype "passive"))
      (node (ref "C33") (pin "2") (pinfunction "2_2") (pintype "passive"))
      (node (ref "C34") (pin "2") (pinfunction "2_2") (pintype "passive"))
      (node (ref "C4") (pin "2") (pinfunction "2_2") (pintype "passive"))
      (node (ref "C5") (pin "2") (pinfunction "2_2") (pintype "passive"))
      (node (ref "C6") (pin "2") (pinfunction "2_2") (pintype "passive"))
      (node (ref "C7") (pin "2") (pinfunction "2_2") (pintype "passive"))
      (node (ref "C8") (pin "2") (pinfunction "2_2") (pintype "passive"))
      (node (ref "C9") (pin "2") (pinfunction "2_2") (pintype "passive"))
      (node (ref "ESP1") (pin "57") (pinfunction "EPAD_57") (pintype "power_in"))
      (node (ref "JP1") (pin "2") (pintype "passive"))
      (node (ref "JP10") (pin "1") (pintype "passive"))
      (node (ref "JP2") (pin "A1") (pinfunction "GND_A_A1") (pintype "power_in"))
      (node (ref "JP2") (pin "A12") (pinfunction "GND_A_A12") (pintype "power_in"))
      (node (ref "JP2") (pin "B1") (pinfunction "GND_B_B1") (pintype "power_in"))
      (node (ref "JP2") (pin "B12") (pinfunction "GND_B_B12") (pintype "power_in"))
      (node (ref "JP2") (pin "S1") (pinfunction "SHELL_GND_S1") (pintype "power_in"))
      (node (ref "JP2") (pin "S2") (pinfunction "SHELL_GND_S2") (pintype "power_in"))
      (node (ref "JP2") (pin "S3") (pinfunction "SHELL_GND_S3") (pintype "power_in"))
      (node (ref "JP2") (pin "S4") (pinfunction "SHELL_GND_S4") (pintype "power_in"))
      (node (ref "JP3") (pin "1") (pintype "passive"))
      (node (ref "M1") (pin "16") (pinfunction "VSS@2_16") (pintype "power_in"))
      (node (ref "M1") (pin "21") (pinfunction "VSS@3_21") (pintype "power_in"))
      (node (ref "M1") (pin "23") (pinfunction "VSS@4_23") (pintype "power_in"))
      (node (ref "M1") (pin "24") (pinfunction "VSS@5_24") (pintype "power_in"))
      (node (ref "M1") (pin "8") (pinfunction "VSS@1_8") (pintype "power_in"))
      (node (ref "R1") (pin "2") (pinfunction "2_2") (pintype "passive"))
      (node (ref "R10") (pin "2") (pinfunction "2_2") (pintype "passive"))
      (node (ref "R12") (pin "2") (pinfunction "2_2") (pintype "passive"))
      (node (ref "R14") (pin "1") (pinfunction "1_1") (pintype "passive"))
      (node (ref "R19") (pin "2") (pinfunction "2_2") (pintype "passive"))
      (node (ref "R20") (pin "1") (pinfunction "1_1") (pintype "passive"))
      (node (ref "R3") (pin "1") (pinfunction "1_1") (pintype "passive"))
      (node (ref "R4") (pin "2") (pinfunction "2_2") (pintype "passive"))
      (node (ref "R5") (pin "2") (pinfunction "2_2") (pintype "passive"))
      (node (ref "R6") (pin "2") (pinfunction "2_2") (pintype "passive"))
      (node (ref "R8") (pin "2") (pinfunction "2_2") (pintype "passive"))
      (node (ref "R9") (pin "2") (pinfunction "2_2") (pintype "passive"))
      (node (ref "SW*1") (pin "1") (pinfunction "1_1") (pintype "passive"))
      (node (ref "SW*2") (pin "1") (pinfunction "1_1") (pintype "passive"))
      (node (ref "U1") (pin "3") (pinfunction "GND_3") (pintype "input"))
      (node (ref "U10") (pin "12") (pinfunction "GND_12") (pintype "power_in"))
      (node (ref "U10") (pin "4") (pinfunction "PGND_4") (pintype "power_in"))
      (node (ref "U11") (pin "16") (pinfunction "PGND_16") (pintype "power_in"))
      (node (ref "U2") (pin "11") (pinfunction "FSYNC_11") (pintype "input"))
      (node (ref "U2") (pin "18") (pinfunction "GND_18") (pintype "power_in"))
      (node (ref "U2") (pin "20") (pinfunction "RESV_20_20") (pintype "power_in"))
      (node (ref "U2") (pin "25") (pinfunction "EXP_25") (pintype "passive"))
      (node (ref "U4") (pin "2") (pinfunction "GND_2") (pintype "power_in"))
      (node (ref "U5") (pin "1") (pinfunction "GND_1") (pintype "power_in"))
      (node (ref "U6") (pin "4") (pinfunction "GND_4") (pintype "passive"))
      (node (ref "U7") (pin "2") (pinfunction "VS_2") (pintype "passive"))
      (node (ref "U8") (pin "4") (pinfunction "GND_4") (pintype "power_in"))
      (node (ref "U8") (pin "5") (pinfunction "A2_5") (pintype "input"))
      (node (ref "U8") (pin "6") (pinfunction "A1_6") (pintype "input"))
      (node (ref "U8") (pin "7") (pinfunction "A0_7") (pintype "input"))
      (node (ref "U8") (pin "9") (pinfunction "EP_9") (pintype "power_in"))
      (node (ref "U9") (pin "4") (pinfunction "L/R_4") (pintype "bidirectional"))
      (node (ref "U9") (pin "5") (pinfunction "GND_5") (pintype "passive"))
      (node (ref "U9") (pin "8") (pinfunction "GND_8") (pintype "passive"))
      (node (ref "X1") (pin "2") (pinfunction "2_2") (pintype "passive"))
      (node (ref "X1") (pin "4") (pinfunction "4_4") (pintype "passive"))
    )
    (net (code "49") (name "GNDA") (class "Default")
      (node (ref "C35") (pin "2") (pinfunction "2_2") (pintype "passive"))
      (node (ref "C36") (pin "2") (pinfunction "2_2") (pintype "passive"))
      (node (ref "C38") (pin "2") (pinfunction "2_2") (pintype "passive"))
      (node (ref "R20") (pin "2") (pinfunction "2_2") (pintype "passive"))
      (node (ref "R21") (pin "1") (pinfunction "1_1") (pintype "passive"))
      (node (ref "U11") (pin "18") (pinfunction "GND_ANA_18") (pintype "power_in"))
    )
    (net (code "50") (name "GNDD") (class "Default")
      (node (ref "C31") (pin "1") (pinfunction "1_1") (pintype "passive"))
      (node (ref "C32") (pin "1") (pinfunction "1_1") (pintype "passive"))
      (node (ref "R21") (pin "2") (pinfunction "2_2") (pintype "passive"))
      (node (ref "U11") (pin "17") (pinfunction "GND_DIG_17") (pintype "power_in"))
    )
    (net (code "51") (name "Net-(ANT1-FEED)") (class "Default")
      (node (ref "ANT1") (pin "2") (pinfunction "FEED_2") (pintype "passive"))
      (node (ref "C13") (pin "1") (pinfunction "1_1") (pintype "passive"))
      (node (ref "L1") (pin "1") (pinfunction "1_1") (pintype "passive"))
    )
    (net (code "52") (name "Net-(JP2-RX+_A)") (class "Default")
      (node (ref "JP2") (pin "A10") (pinfunction "RX+_A_A10") (pintype "power_in"))
      (node (ref "JP2") (pin "A11") (pinfunction "RX-_A_A11") (pintype "power_in"))
    )
    (net (code "53") (name "Net-(JP2-RX+_B)") (class "Default")
      (node (ref "JP2") (pin "B10") (pinfunction "RX+_B_B10") (pintype "power_in"))
      (node (ref "JP2") (pin "B11") (pinfunction "RX-_B_B11") (pintype "power_in"))
    )
    (net (code "54") (name "Net-(JP2-TX+_A)") (class "Default")
      (node (ref "JP2") (pin "A2") (pinfunction "TX+_A_A2") (pintype "power_in"))
      (node (ref "JP2") (pin "A3") (pinfunction "TX-_A_A3") (pintype "power_in"))
    )
    (net (code "55") (name "Net-(JP2-TX+_B)") (class "Default")
      (node (ref "JP2") (pin "B2") (pinfunction "TX+_B_B2") (pintype "power_in"))
      (node (ref "JP2") (pin "B3") (pinfunction "TX-_B_B3") (pintype "power_in"))
    )
    (net (code "56") (name "Net-(LED1-A)") (class "Default")
      (node (ref "LED1") (pin "1") (pinfunction "A_1") (pintype "passive"))
      (node (ref "LED2") (pin "1") (pinfunction "A_1") (pintype "passive"))
      (node (ref "R2") (pin "2") (pinfunction "2_2") (pintype "passive"))
    )
    (net (code "57") (name "Net-(LED1-K)") (class "Default")
      (node (ref "LED1") (pin "2") (pinfunction "K_2") (pintype "passive"))
      (node (ref "U1") (pin "6") (pinfunction "~{DONE}_6") (pintype "passive"))
    )
    (net (code "58") (name "Net-(LED2-K)") (class "Default")
      (node (ref "LED2") (pin "2") (pinfunction "K_2") (pintype "passive"))
      (node (ref "U1") (pin "7") (pinfunction "~{CHRG}_7") (pintype "power_in"))
    )
    (net (code "59") (name "Net-(R15-Pad2)") (class "Default")
      (node (ref "R15") (pin "2") (pinfunction "2_2") (pintype "passive"))
      (node (ref "SW*1") (pin "2") (pinfunction "2_2") (pintype "passive"))
    )
    (net (code "60") (name "Net-(R17-Pad2)") (class "Default")
      (node (ref "R17") (pin "2") (pinfunction "2_2") (pintype "passive"))
      (node (ref "SW*2") (pin "2") (pinfunction "2_2") (pintype "passive"))
    )
    (net (code "61") (name "Net-(U1-PROG)") (class "Default")
      (node (ref "R1") (pin "1") (pinfunction "1_1") (pintype "passive"))
      (node (ref "U1") (pin "2") (pinfunction "PROG_2") (pintype "input"))
    )
    (net (code "62") (name "Net-(U2-AD0{slash}SDO)") (class "Default")
      (node (ref "R9") (pin "1") (pinfunction "1_1") (pintype "passive"))
      (node (ref "U2") (pin "9") (pinfunction "AD0/SDO_9") (pintype "output"))
    )
    (net (code "63") (name "Net-(U2-REGOUT)") (class "Default")
      (node (ref "C8") (pin "1") (pinfunction "1_1") (pintype "passive"))
      (node (ref "U2") (pin "10") (pinfunction "REGOUT_10") (pintype "output"))
    )
    (net (code "64") (name "Net-(U3-D)") (class "Default")
      (node (ref "U3") (pin "3") (pinfunction "D_3") (pintype "passive"))
      (node (ref "Z2") (pin "1") (pinfunction "A_1") (pintype "passive"))
    )
    (net (code "65") (name "Net-(U4-ADJ)") (class "Default")
      (node (ref "R10") (pin "1") (pinfunction "1_1") (pintype "passive"))
      (node (ref "R7") (pin "2") (pinfunction "2_2") (pintype "passive"))
      (node (ref "U4") (pin "4") (pinfunction "ADJ_4") (pintype "power_in"))
    )
    (net (code "66") (name "Net-(U8-OS)") (class "Default")
      (node (ref "RA1") (pin "8") (pinfunction "8_8") (pintype "passive"))
      (node (ref "U8") (pin "3") (pinfunction "OS_3") (pintype "output"))
    )
    (net (code "67") (name "Net-(U11-C1_N)") (class "Default")
      (node (ref "C37") (pin "2") (pinfunction "2_2") (pintype "passive"))
      (node (ref "U11") (pin "20") (pinfunction "C1_N_20") (pintype "bidirectional"))
    )
    (net (code "68") (name "Net-(U11-C1_P)") (class "Default")
      (node (ref "C37") (pin "1") (pinfunction "1_1") (pintype "passive"))
      (node (ref "U11") (pin "21") (pinfunction "C1_P_21") (pintype "bidirectional"))
    )
    (net (code "69") (name "Net-(U11-VREF)") (class "Default")
      (node (ref "C38") (pin "1") (pinfunction "1_1") (pintype "passive"))
      (node (ref "U11") (pin "19") (pinfunction "VREF_19") (pintype "input"))
    )
    (net (code "70") (name "REGIN") (class "Default")
      (node (ref "C5") (pin "1") (pinfunction "1_1") (pintype "passive"))
      (node (ref "C7") (pin "1") (pinfunction "1_1") (pintype "passive"))
      (node (ref "U4") (pin "1") (pinfunction "IN_1") (pintype "power_in"))
      (node (ref "U5") (pin "2") (pinfunction "IN_2") (pintype "power_in"))
      (node (ref "Z1") (pin "2") (pinfunction "K_2") (pintype "passive"))
      (node (ref "Z2") (pin "2") (pinfunction "K_2") (pintype "passive"))
    )
    (net (code "71") (name "VBAT") (class "Default")
      (node (ref "JP1") (pin "1") (pintype "passive"))
      (node (ref "R11") (pin "1") (pinfunction "1_1") (pintype "passive"))
      (node (ref "U1") (pin "5") (pinfunction "VBAT_5") (pintype "power_in"))
      (node (ref "U3") (pin "2") (pinfunction "S_2") (pintype "passive"))
    )
    (net (code "72") (name "VDD_SPI") (class "Default")
      (node (ref "C24") (pin "1") (pinfunction "1_1") (pintype "passive"))
      (node (ref "ESP1") (pin "29") (pinfunction "VDD_SPI_29") (pintype "power_in"))
      (node (ref "R13") (pin "1") (pinfunction "1_1") (pintype "passive"))
      (node (ref "U6") (pin "8") (pinfunction "VCC_8") (pintype "power_in"))
    )
    (net (code "73") (name "unconnected-(ESP1-MTCK-Pad44)") (class "Default")
      (node (ref "ESP1") (pin "44") (pinfunction "MTCK_44") (pintype "bidirectional"))
    )
    (net (code "74") (name "unconnected-(ESP1-MTDI-Pad47)") (class "Default")
      (node (ref "ESP1") (pin "47") (pinfunction "MTDI_47") (pintype "bidirectional"))
    )
    (net (code "75") (name "unconnected-(ESP1-MTDO-Pad45)") (class "Default")
      (node (ref "ESP1") (pin "45") (pinfunction "MTDO_45") (pintype "bidirectional"))
    )
    (net (code "76") (name "unconnected-(ESP1-MTMS-Pad48)") (class "Default")
      (node (ref "ESP1") (pin "48") (pinfunction "MTMS_48") (pintype "bidirectional"))
    )
    (net (code "77") (name "unconnected-(ESP1-SPICLK_P-Pad37)") (class "Default")
      (node (ref "ESP1") (pin "37") (pinfunction "SPICLK_P_37") (pintype "bidirectional"))
    )
    (net (code "78") (name "unconnected-(ESP1-SPICS1-Pad28)") (class "Default")
      (node (ref "ESP1") (pin "28") (pinfunction "SPICS1_28") (pintype "bidirectional"))
    )
    (net (code "79") (name "unconnected-(ESP1-XTAL_32K_N-Pad22)") (class "Default")
      (node (ref "ESP1") (pin "22") (pinfunction "XTAL_32K_N_22") (pintype "passive"))
    )
    (net (code "80") (name "unconnected-(ESP1-XTAL_32K_P-Pad21)") (class "Default")
      (node (ref "ESP1") (pin "21") (pinfunction "XTAL_32K_P_21") (pintype "passive"))
    )
    (net (code "81") (name "unconnected-(JP2-CC1-PadA5)") (class "Default")
      (node (ref "JP2") (pin "A5") (pinfunction "CC1_A5") (pintype "bidirectional+no_connect"))
    )
    (net (code "82") (name "unconnected-(JP2-CC2-PadB5)") (class "Default")
      (node (ref "JP2") (pin "B5") (pinfunction "CC2_B5") (pintype "bidirectional+no_connect"))
    )
    (net (code "83") (name "unconnected-(JP2-SBU1-PadA8)") (class "Default")
      (node (ref "JP2") (pin "A8") (pinfunction "SBU1_A8") (pintype "bidirectional+no_connect"))
    )
    (net (code "84") (name "unconnected-(JP2-SBU2-PadB8)") (class "Default")
      (node (ref "JP2") (pin "B8") (pinfunction "SBU2_B8") (pintype "bidirectional+no_connect"))
    )
    (net (code "85") (name "unconnected-(JP10-Pad3)") (class "Default")
      (node (ref "JP10") (pin "3") (pintype "passive"))
    )
    (net (code "86") (name "unconnected-(M1-GPIO0-Pad15)") (class "Default")
      (node (ref "M1") (pin "15") (pinfunction "GPIO0_15") (pintype "bidirectional+no_connect"))
    )
    (net (code "87") (name "unconnected-(M1-GPIO1-Pad14)") (class "Default")
      (node (ref "M1") (pin "14") (pinfunction "GPIO1_14") (pintype "bidirectional+no_connect"))
    )
    (net (code "88") (name "unconnected-(M1-GPIO2-Pad13)") (class "Default")
      (node (ref "M1") (pin "13") (pinfunction "GPIO2_13") (pintype "bidirectional+no_connect"))
    )
    (net (code "89") (name "unconnected-(M1-GPIO3-Pad12)") (class "Default")
      (node (ref "M1") (pin "12") (pinfunction "GPIO3_12") (pintype "bidirectional+no_connect"))
    )
    (net (code "90") (name "unconnected-(M1-GPIO4-Pad11)") (class "Default")
      (node (ref "M1") (pin "11") (pinfunction "GPIO4_11") (pintype "bidirectional+no_connect"))
    )
    (net (code "91") (name "unconnected-(M1-GPIO5-Pad10)") (class "Default")
      (node (ref "M1") (pin "10") (pinfunction "GPIO5_10") (pintype "bidirectional+no_connect"))
    )
    (net (code "92") (name "unconnected-(M1-GPIO6-Pad9)") (class "Default")
      (node (ref "M1") (pin "9") (pinfunction "GPIO6_9") (pintype "bidirectional+no_connect"))
    )
    (net (code "93") (name "unconnected-(M1-GPIO7-Pad4)") (class "Default")
      (node (ref "M1") (pin "4") (pinfunction "GPIO7_4") (pintype "bidirectional+no_connect"))
    )
    (net (code "94") (name "unconnected-(RA1-Pad7)") (class "Default")
      (node (ref "RA1") (pin "7") (pinfunction "7_7") (pintype "passive"))
    )
    (net (code "95") (name "unconnected-(U2-AUX_CL-Pad7)") (class "Default")
      (node (ref "U2") (pin "7") (pinfunction "AUX_CL_7") (pintype "input+no_connect"))
    )
    (net (code "96") (name "unconnected-(U2-AUX_DA-Pad21)") (class "Default")
      (node (ref "U2") (pin "21") (pinfunction "AUX_DA_21") (pintype "input+no_connect"))
    )
    (net (code "97") (name "unconnected-(U2-NC-Pad2)") (class "Default")
      (node (ref "U2") (pin "2") (pinfunction "NC_2") (pintype "passive+no_connect"))
    )
    (net (code "98") (name "unconnected-(U2-NC-Pad3)") (class "Default")
      (node (ref "U2") (pin "3") (pinfunction "NC_3") (pintype "passive+no_connect"))
    )
    (net (code "99") (name "unconnected-(U2-NC-Pad4)") (class "Default")
      (node (ref "U2") (pin "4") (pinfunction "NC_4") (pintype "passive+no_connect"))
    )
    (net (code "100") (name "unconnected-(U2-NC-Pad5)") (class "Default")
      (node (ref "U2") (pin "5") (pinfunction "NC_5") (pintype "passive+no_connect"))
    )
    (net (code "101") (name "unconnected-(U2-NC-Pad6)") (class "Default")
      (node (ref "U2") (pin "6") (pinfunction "NC_6") (pintype "passive+no_connect"))
    )
    (net (code "102") (name "unconnected-(U2-NC-Pad14)") (class "Default")
      (node (ref "U2") (pin "14") (pinfunction "NC_14") (pintype "passive+no_connect"))
    )
    (net (code "103") (name "unconnected-(U2-NC-Pad15)") (class "Default")
      (node (ref "U2") (pin "15") (pinfunction "NC_15") (pintype "passive+no_connect"))
    )
    (net (code "104") (name "unconnected-(U2-NC-Pad16)") (class "Default")
      (node (ref "U2") (pin "16") (pinfunction "NC_16") (pintype "passive+no_connect"))
    )
    (net (code "105") (name "unconnected-(U2-NC-Pad17)") (class "Default")
      (node (ref "U2") (pin "17") (pinfunction "NC_17") (pintype "passive+no_connect"))
    )
    (net (code "106") (name "unconnected-(U2-RESV_19-Pad19)") (class "Default")
      (node (ref "U2") (pin "19") (pinfunction "RESV_19_19") (pintype "passive+no_connect"))
    )
    (net (code "107") (name "unconnected-(U7-AHLB-Pad4)") (class "Default")
      (node (ref "U7") (pin "4") (pinfunction "AHLB_4") (pintype "passive+no_connect"))
    )
    (net (code "108") (name "unconnected-(U7-TOG-Pad6)") (class "Default")
      (node (ref "U7") (pin "6") (pinfunction "TOG_6") (pintype "passive+no_connect"))
    )
    (net (code "109") (name "unconnected-(U11-ECG_N-Pad4)") (class "Default")
      (node (ref "U11") (pin "4") (pinfunction "ECG_N_4") (pintype "bidirectional"))
    )
    (net (code "110") (name "unconnected-(U11-ECG_P-Pad5)") (class "Default")
      (node (ref "U11") (pin "5") (pinfunction "ECG_P_5") (pintype "bidirectional"))
    )
    (net (code "111") (name "unconnected-(U11-N.C.-1-Pad1)") (class "Default")
      (node (ref "U11") (pin "1") (pinfunction "N.C.-1_1") (pintype "bidirectional+no_connect"))
    )
    (net (code "112") (name "unconnected-(U11-N.C.-2-Pad2)") (class "Default")
      (node (ref "U11") (pin "2") (pinfunction "N.C.-2_2") (pintype "bidirectional+no_connect"))
    )
    (net (code "113") (name "unconnected-(U11-N.C.-3-Pad3)") (class "Default")
      (node (ref "U11") (pin "3") (pinfunction "N.C.-3_3") (pintype "bidirectional+no_connect"))
    )
    (net (code "114") (name "unconnected-(U11-N.C.-4-Pad6)") (class "Default")
      (node (ref "U11") (pin "6") (pinfunction "N.C.-4_6") (pintype "bidirectional+no_connect"))
    )
    (net (code "115") (name "unconnected-(U11-N.C.-5-Pad22)") (class "Default")
      (node (ref "U11") (pin "22") (pinfunction "N.C.-5_22") (pintype "bidirectional+no_connect"))
    )
    (net (code "116") (name "unconnected-(U11-N.C.-6-Pad11)") (class "Default")
      (node (ref "U11") (pin "11") (pinfunction "N.C.-6_11") (pintype "bidirectional+no_connect"))
    )
    (net (code "117") (name "unconnected-(U11-N.C.-7-Pad12)") (class "Default")
      (node (ref "U11") (pin "12") (pinfunction "N.C.-7_12") (pintype "bidirectional+no_connect"))
    )
    (net (code "118") (name "unconnected-(U11-N.C.-Pad10)") (class "Default")
      (node (ref "U11") (pin "10") (pinfunction "N.C._10") (pintype "bidirectional+no_connect"))
    )
  )
)
